# usbasp.net
KiCad netlist of a schematic drawn in EAGLE
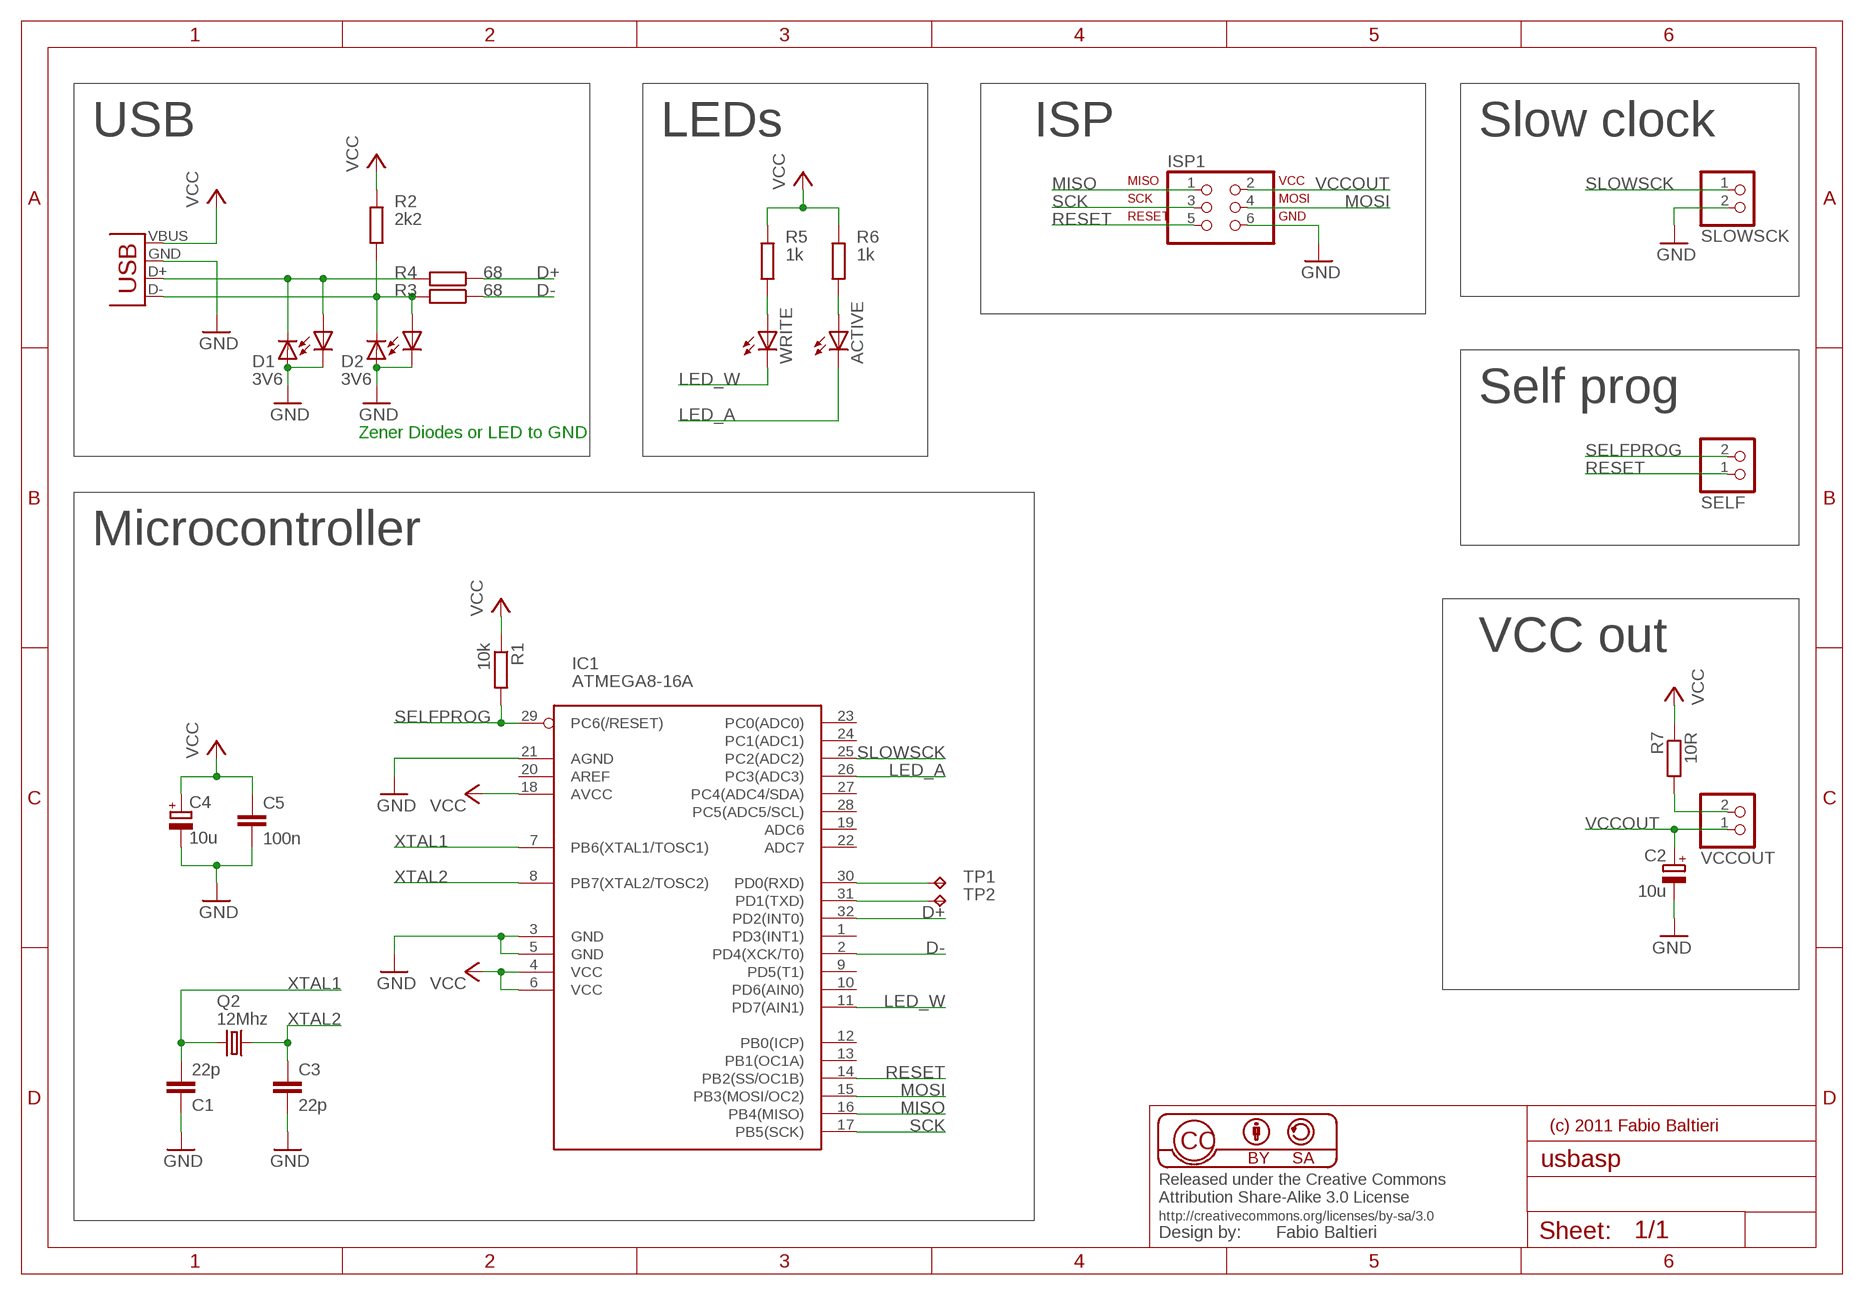
[diagram p0: schematic, sheet 1]

(export (version "E")
  (design (tool "Eeschema 10.0.6"))
  (components
    (comp (ref "ACTIVE")
      (value "LEDCHIP-LED0805")
      (footprint "eagle-import:CHIP-LED0805")
      (libsource (lib "eagle-import") (part "LEDCHIP-LED0805"))
    )
    (comp (ref "C1")
      (value "22p")
      (footprint "eagle-import:C0805")
      (libsource (lib "eagle-import") (part "C-EUC0805"))
    )
    (comp (ref "C2")
      (value "10u")
      (footprint "eagle-import:SMC_A")
      (libsource (lib "eagle-import") (part "CPOL-EUSMCA"))
    )
    (comp (ref "C3")
      (value "22p")
      (footprint "eagle-import:C0805")
      (libsource (lib "eagle-import") (part "C-EUC0805"))
    )
    (comp (ref "C4")
      (value "10u")
      (footprint "eagle-import:SMC_A")
      (libsource (lib "eagle-import") (part "CPOL-EUSMCA"))
    )
    (comp (ref "C5")
      (value "100n")
      (footprint "eagle-import:C0805")
      (libsource (lib "eagle-import") (part "C-EUC0805"))
    )
    (comp (ref "D1")
      (value "3V6")
      (footprint "eagle-import:SMA-DIODE")
      (libsource (lib "eagle-import") (part "DIODESMA"))
    )
    (comp (ref "D2")
      (value "3V6")
      (footprint "eagle-import:SMA-DIODE")
      (libsource (lib "eagle-import") (part "DIODESMA"))
    )
    (comp (ref "IC1")
      (value "ATMEGA8-16A")
      (footprint "eagle-import:TQFP32-08")
      (libsource (lib "eagle-import") (part "ATMEGA8A-16"))
    )
    (comp (ref "ISP1")
      (value "ISP-AVR910SMD")
      (footprint "eagle-import:2X03_BORDER")
      (libsource (lib "eagle-import") (part "ISP-AVR910SMD"))
    )
    (comp (ref "LED1")
      (value "LEDCHIP-LED0805")
      (footprint "eagle-import:CHIP-LED0805")
      (libsource (lib "eagle-import") (part "LEDCHIP-LED0805"))
    )
    (comp (ref "LED2")
      (value "LEDCHIP-LED0805")
      (footprint "eagle-import:CHIP-LED0805")
      (libsource (lib "eagle-import") (part "LEDCHIP-LED0805"))
    )
    (comp (ref "Q2")
      (value "12Mhz")
      (footprint "eagle-import:HC49US")
      (libsource (lib "eagle-import") (part "CRYSTALHC49US"))
    )
    (comp (ref "R1")
      (value "10k")
      (footprint "eagle-import:M0805")
      (libsource (lib "eagle-import") (part "R-EU_M0805"))
    )
    (comp (ref "R2")
      (value "2k2")
      (footprint "eagle-import:M0805")
      (libsource (lib "eagle-import") (part "R-EU_M0805"))
    )
    (comp (ref "R3")
      (value "68")
      (footprint "eagle-import:M0805")
      (libsource (lib "eagle-import") (part "R-EU_M0805"))
    )
    (comp (ref "R4")
      (value "68")
      (footprint "eagle-import:M0805")
      (libsource (lib "eagle-import") (part "R-EU_M0805"))
    )
    (comp (ref "R5")
      (value "1k")
      (footprint "eagle-import:M0805")
      (libsource (lib "eagle-import") (part "R-EU_M0805"))
    )
    (comp (ref "R6")
      (value "1k")
      (footprint "eagle-import:M0805")
      (libsource (lib "eagle-import") (part "R-EU_M0805"))
    )
    (comp (ref "R7")
      (value "10R")
      (footprint "eagle-import:M0805")
      (libsource (lib "eagle-import") (part "R-EU_M0805"))
    )
    (comp (ref "SELF")
      (value "PINHD-1X2")
      (footprint "eagle-import:1X02")
      (libsource (lib "eagle-import") (part "PINHD-1X2"))
    )
    (comp (ref "SLOWSCK")
      (value "PINHD-1X2")
      (footprint "eagle-import:1X02")
      (libsource (lib "eagle-import") (part "PINHD-1X2"))
    )
    (comp (ref "TP1")
      (value "TPB1,27")
      (footprint "eagle-import:B1,27")
      (libsource (lib "eagle-import") (part "TPB1,27"))
    )
    (comp (ref "TP2")
      (value "TPB1,27")
      (footprint "eagle-import:B1,27")
      (libsource (lib "eagle-import") (part "TPB1,27"))
    )
    (comp (ref "VCCOUT")
      (value "PINHD-1X2")
      (footprint "eagle-import:1X02")
      (libsource (lib "eagle-import") (part "PINHD-1X2"))
    )
    (comp (ref "WRITE")
      (value "LEDCHIP-LED0805")
      (footprint "eagle-import:CHIP-LED0805")
      (libsource (lib "eagle-import") (part "LEDCHIP-LED0805"))
    )
    (comp (ref "X1")
      (value "USB-A-H")
      (footprint "eagle-import:USB-A-H")
      (libsource (lib "eagle-import") (part "USB-A-H"))
    )
  )
  (nets
    (net (code "1") (name "/D+") (class "Default")
      (node (ref "IC1") (pin "32") (pinfunction "PD2(INT0)_32") (pintype "bidirectional"))
      (node (ref "R4") (pin "1") (pinfunction "1_1") (pintype "passive"))
    )
    (net (code "2") (name "/D-") (class "Default")
      (node (ref "IC1") (pin "2") (pinfunction "PD4(XCK/T0)_2") (pintype "bidirectional"))
      (node (ref "R3") (pin "1") (pinfunction "1_1") (pintype "passive"))
    )
    (net (code "3") (name "/LED_A") (class "Default")
      (node (ref "ACTIVE") (pin "C") (pinfunction "C_C") (pintype "passive"))
      (node (ref "IC1") (pin "26") (pinfunction "PC3(ADC3)_26") (pintype "bidirectional"))
    )
    (net (code "4") (name "/LED_W") (class "Default")
      (node (ref "IC1") (pin "11") (pinfunction "PD7(AIN1)_11") (pintype "bidirectional"))
      (node (ref "WRITE") (pin "C") (pinfunction "C_C") (pintype "passive"))
    )
    (net (code "5") (name "/MISO") (class "Default")
      (node (ref "IC1") (pin "16") (pinfunction "PB4(MISO)_16") (pintype "bidirectional"))
      (node (ref "ISP1") (pin "1") (pinfunction "1_1") (pintype "passive"))
    )
    (net (code "6") (name "/MOSI") (class "Default")
      (node (ref "IC1") (pin "15") (pinfunction "PB3(MOSI/OC2)_15") (pintype "bidirectional"))
      (node (ref "ISP1") (pin "4") (pinfunction "4_4") (pintype "passive"))
    )
    (net (code "7") (name "/RESET") (class "Default")
      (node (ref "IC1") (pin "14") (pinfunction "PB2(SS/OC1B)_14") (pintype "bidirectional"))
      (node (ref "ISP1") (pin "5") (pinfunction "5_5") (pintype "passive"))
      (node (ref "SELF") (pin "1") (pinfunction "1_1") (pintype "passive"))
    )
    (net (code "8") (name "/SCK") (class "Default")
      (node (ref "IC1") (pin "17") (pinfunction "PB5(SCK)_17") (pintype "bidirectional"))
      (node (ref "ISP1") (pin "3") (pinfunction "3_3") (pintype "passive"))
    )
    (net (code "9") (name "/SELFPROG") (class "Default")
      (node (ref "IC1") (pin "29") (pinfunction "PC6(/RESET)_29") (pintype "bidirectional"))
      (node (ref "R1") (pin "2") (pinfunction "2_2") (pintype "passive"))
      (node (ref "SELF") (pin "2") (pinfunction "2_2") (pintype "passive"))
    )
    (net (code "10") (name "/SLOWSCK") (class "Default")
      (node (ref "IC1") (pin "25") (pinfunction "PC2(ADC2)_25") (pintype "bidirectional"))
      (node (ref "SLOWSCK") (pin "1") (pinfunction "1_1") (pintype "passive"))
    )
    (net (code "11") (name "/VCCOUT") (class "Default")
      (node (ref "C2") (pin "+") (pinfunction "+_+") (pintype "passive"))
      (node (ref "ISP1") (pin "2") (pinfunction "2_2") (pintype "passive"))
      (node (ref "VCCOUT") (pin "1") (pinfunction "1_1") (pintype "passive"))
    )
    (net (code "12") (name "/XTAL1") (class "Default")
      (node (ref "C1") (pin "2") (pinfunction "2_2") (pintype "passive"))
      (node (ref "IC1") (pin "7") (pinfunction "PB6(XTAL1/TOSC1)_7") (pintype "bidirectional"))
      (node (ref "Q2") (pin "2") (pinfunction "2_2") (pintype "passive"))
    )
    (net (code "13") (name "/XTAL2") (class "Default")
      (node (ref "C3") (pin "2") (pinfunction "2_2") (pintype "passive"))
      (node (ref "IC1") (pin "8") (pinfunction "PB7(XTAL2/TOSC2)_8") (pintype "bidirectional"))
      (node (ref "Q2") (pin "1") (pinfunction "1_1") (pintype "passive"))
    )
    (net (code "14") (name "GND") (class "Default")
      (node (ref "C1") (pin "1") (pinfunction "1_1") (pintype "passive"))
      (node (ref "C2") (pin "-") (pinfunction "-_-") (pintype "passive"))
      (node (ref "C3") (pin "1") (pinfunction "1_1") (pintype "passive"))
      (node (ref "C4") (pin "-") (pinfunction "-_-") (pintype "passive"))
      (node (ref "C5") (pin "2") (pinfunction "2_2") (pintype "passive"))
      (node (ref "D1") (pin "A") (pinfunction "A_A") (pintype "passive"))
      (node (ref "D2") (pin "A") (pinfunction "A_A") (pintype "passive"))
      (node (ref "IC1") (pin "21") (pinfunction "AGND_21") (pintype "bidirectional"))
      (node (ref "IC1") (pin "3") (pinfunction "GND_3") (pintype "bidirectional"))
      (node (ref "IC1") (pin "5") (pinfunction "GND_5") (pintype "bidirectional"))
      (node (ref "ISP1") (pin "6") (pinfunction "6_6") (pintype "passive"))
      (node (ref "LED1") (pin "C") (pinfunction "C_C") (pintype "passive"))
      (node (ref "LED2") (pin "C") (pinfunction "C_C") (pintype "passive"))
      (node (ref "SLOWSCK") (pin "2") (pinfunction "2_2") (pintype "passive"))
      (node (ref "X1") (pin "GND") (pinfunction "VBUS_GND") (pintype "bidirectional"))
    )
    (net (code "15") (name "Net-(ACTIVE-PadA)") (class "Default")
      (node (ref "ACTIVE") (pin "A") (pinfunction "A_A") (pintype "passive"))
      (node (ref "R6") (pin "2") (pinfunction "2_2") (pintype "passive"))
    )
    (net (code "16") (name "Net-(IC1-PD0(RXD))") (class "Default")
      (node (ref "IC1") (pin "30") (pinfunction "PD0(RXD)_30") (pintype "bidirectional"))
      (node (ref "TP1") (pin "TP") (pinfunction "TP_TP") (pintype "input"))
    )
    (net (code "17") (name "Net-(IC1-PD1(TXD))") (class "Default")
      (node (ref "IC1") (pin "31") (pinfunction "PD1(TXD)_31") (pintype "bidirectional"))
      (node (ref "TP2") (pin "TP") (pinfunction "TP_TP") (pintype "input"))
    )
    (net (code "18") (name "Net-(R5-Pad2)") (class "Default")
      (node (ref "R5") (pin "2") (pinfunction "2_2") (pintype "passive"))
      (node (ref "WRITE") (pin "A") (pinfunction "A_A") (pintype "passive"))
    )
    (net (code "19") (name "Net-(R7-Pad2)") (class "Default")
      (node (ref "R7") (pin "2") (pinfunction "2_2") (pintype "passive"))
      (node (ref "VCCOUT") (pin "2") (pinfunction "2_2") (pintype "passive"))
    )
    (net (code "20") (name "Net-(X1-D+)") (class "Default")
      (node (ref "D2") (pin "C") (pinfunction "C_C") (pintype "passive"))
      (node (ref "LED2") (pin "A") (pinfunction "A_A") (pintype "passive"))
      (node (ref "R2") (pin "1") (pinfunction "1_1") (pintype "passive"))
      (node (ref "R3") (pin "2") (pinfunction "2_2") (pintype "passive"))
      (node (ref "X1") (pin "D-") (pinfunction "D+_D-") (pintype "bidirectional"))
    )
    (net (code "21") (name "Net-(X1-D-)") (class "Default")
      (node (ref "D1") (pin "C") (pinfunction "C_C") (pintype "passive"))
      (node (ref "LED1") (pin "A") (pinfunction "A_A") (pintype "passive"))
      (node (ref "R4") (pin "2") (pinfunction "2_2") (pintype "passive"))
      (node (ref "X1") (pin "D+") (pinfunction "D-_D+") (pintype "bidirectional"))
    )
    (net (code "22") (name "VCC") (class "Default")
      (node (ref "C4") (pin "+") (pinfunction "+_+") (pintype "passive"))
      (node (ref "C5") (pin "1") (pinfunction "1_1") (pintype "passive"))
      (node (ref "IC1") (pin "18") (pinfunction "AVCC_18") (pintype "bidirectional"))
      (node (ref "IC1") (pin "4") (pinfunction "VCC_4") (pintype "bidirectional"))
      (node (ref "IC1") (pin "6") (pinfunction "VCC_6") (pintype "bidirectional"))
      (node (ref "R1") (pin "1") (pinfunction "1_1") (pintype "passive"))
      (node (ref "R2") (pin "2") (pinfunction "2_2") (pintype "passive"))
      (node (ref "R5") (pin "1") (pinfunction "1_1") (pintype "passive"))
      (node (ref "R6") (pin "1") (pinfunction "1_1") (pintype "passive"))
      (node (ref "R7") (pin "1") (pinfunction "1_1") (pintype "passive"))
      (node (ref "X1") (pin "VBUS") (pinfunction "GND_VBUS") (pintype "bidirectional"))
    )
    (net (code "23") (name "unconnected-(IC1-ADC6-Pad19)") (class "Default")
      (node (ref "IC1") (pin "19") (pinfunction "ADC6_19") (pintype "bidirectional"))
    )
    (net (code "24") (name "unconnected-(IC1-ADC7-Pad22)") (class "Default")
      (node (ref "IC1") (pin "22") (pinfunction "ADC7_22") (pintype "bidirectional"))
    )
    (net (code "25") (name "unconnected-(IC1-AREF-Pad20)") (class "Default")
      (node (ref "IC1") (pin "20") (pinfunction "AREF_20") (pintype "bidirectional"))
    )
    (net (code "26") (name "unconnected-(IC1-PB0(ICP)-Pad12)") (class "Default")
      (node (ref "IC1") (pin "12") (pinfunction "PB0(ICP)_12") (pintype "bidirectional"))
    )
    (net (code "27") (name "unconnected-(IC1-PB1(OC1A)-Pad13)") (class "Default")
      (node (ref "IC1") (pin "13") (pinfunction "PB1(OC1A)_13") (pintype "bidirectional"))
    )
    (net (code "28") (name "unconnected-(IC1-PC0(ADC0)-Pad23)") (class "Default")
      (node (ref "IC1") (pin "23") (pinfunction "PC0(ADC0)_23") (pintype "bidirectional"))
    )
    (net (code "29") (name "unconnected-(IC1-PC1(ADC1)-Pad24)") (class "Default")
      (node (ref "IC1") (pin "24") (pinfunction "PC1(ADC1)_24") (pintype "bidirectional"))
    )
    (net (code "30") (name "unconnected-(IC1-PC4(ADC4{slash}SDA)-Pad27)") (class "Default")
      (node (ref "IC1") (pin "27") (pinfunction "PC4(ADC4/SDA)_27") (pintype "bidirectional"))
    )
    (net (code "31") (name "unconnected-(IC1-PC5(ADC5{slash}SCL)-Pad28)") (class "Default")
      (node (ref "IC1") (pin "28") (pinfunction "PC5(ADC5/SCL)_28") (pintype "bidirectional"))
    )
    (net (code "32") (name "unconnected-(IC1-PD3(INT1)-Pad1)") (class "Default")
      (node (ref "IC1") (pin "1") (pinfunction "PD3(INT1)_1") (pintype "bidirectional"))
    )
    (net (code "33") (name "unconnected-(IC1-PD5(T1)-Pad9)") (class "Default")
      (node (ref "IC1") (pin "9") (pinfunction "PD5(T1)_9") (pintype "bidirectional"))
    )
    (net (code "34") (name "unconnected-(IC1-PD6(AIN0)-Pad10)") (class "Default")
      (node (ref "IC1") (pin "10") (pinfunction "PD6(AIN0)_10") (pintype "bidirectional"))
    )
  )
)
